# SparkFun_lsm9ds0-breakout.net
KiCad netlist of a schematic drawn in EAGLE
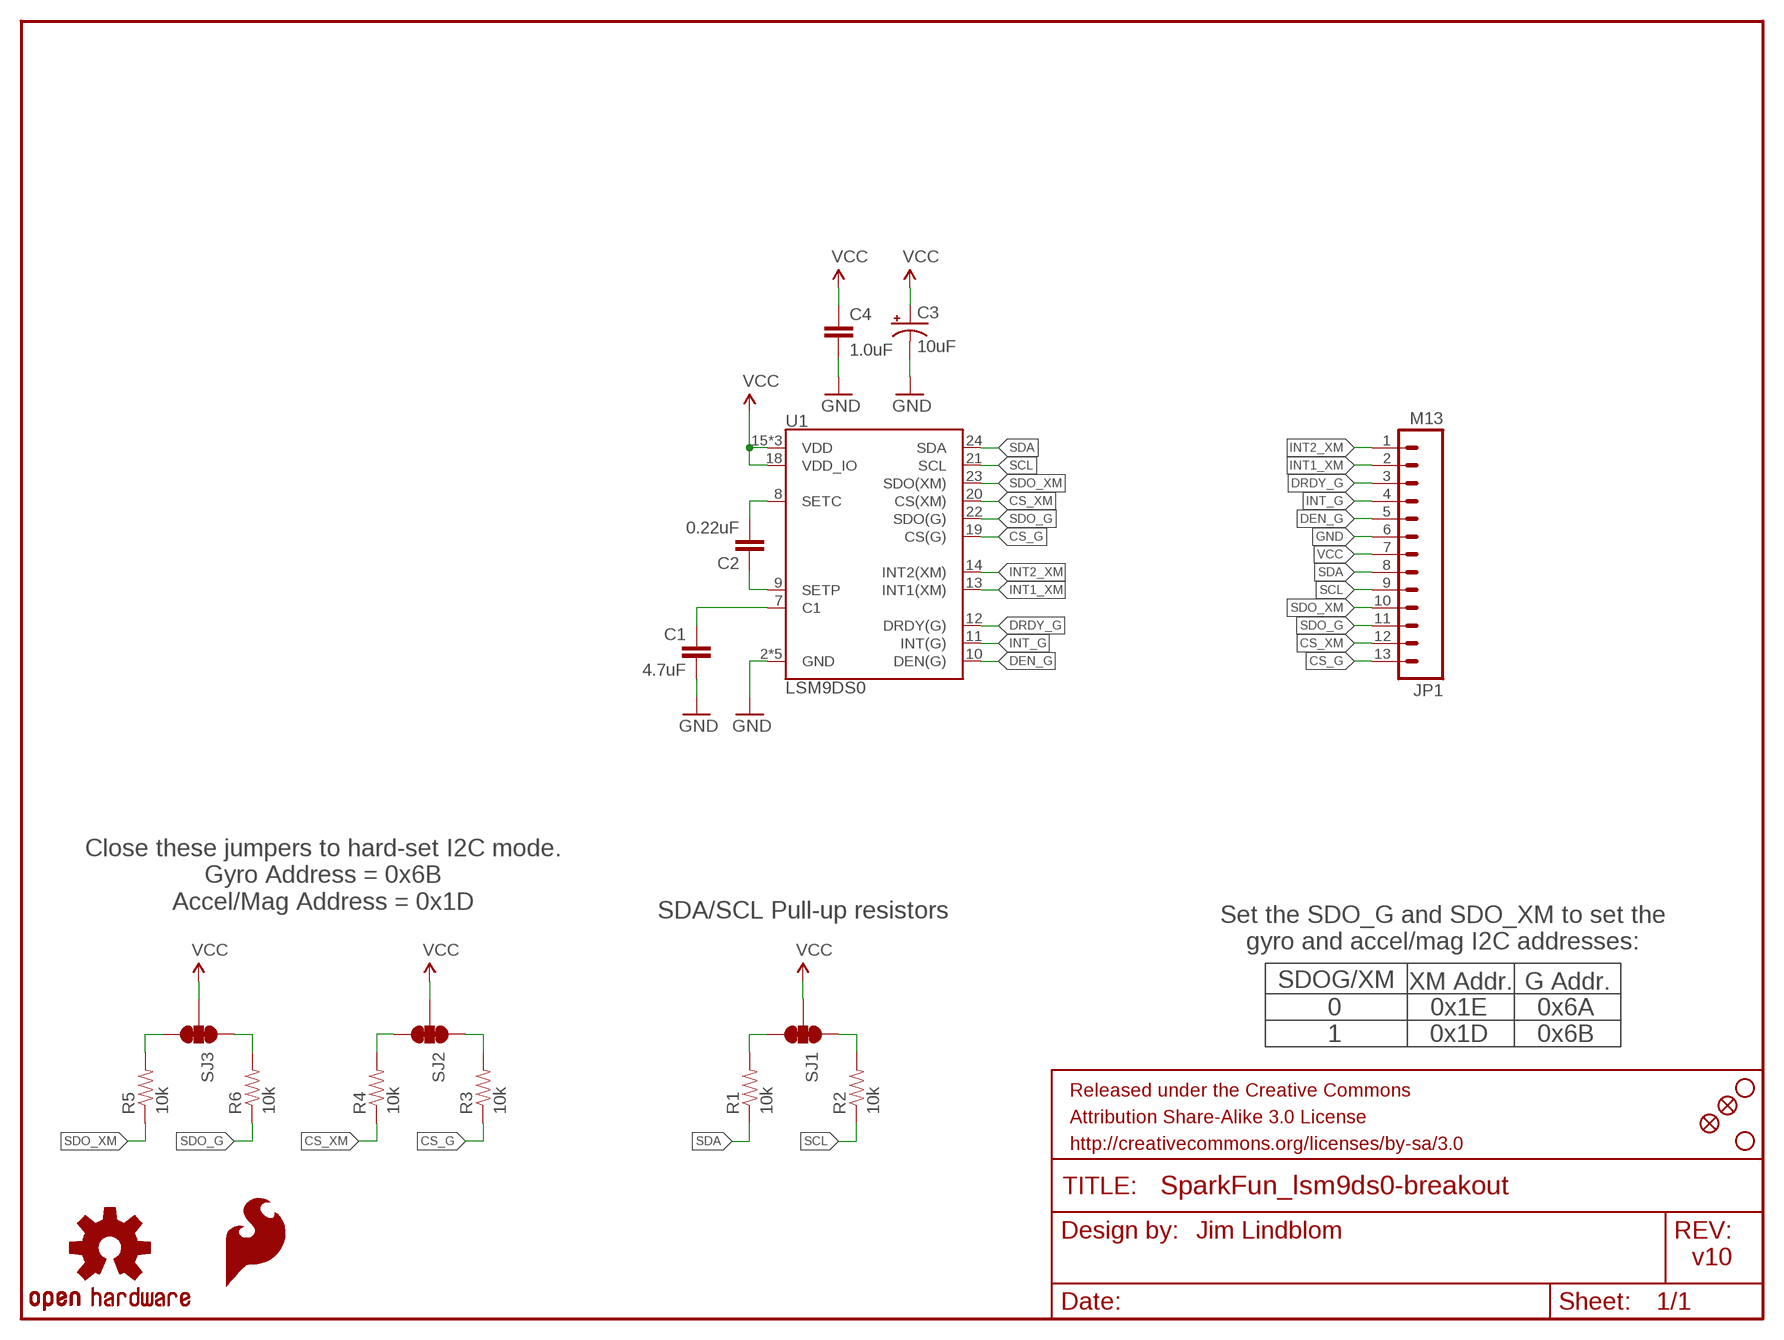
[diagram p0: schematic, sheet 1]

(export (version "E")
  (design (tool "Eeschema 10.0.6"))
  (components
    (comp (ref "C1")
      (value "4.7uF")
      (footprint "eagle-import:0603-CAP")
      (libsource (lib "eagle-import") (part "4.7UF-6.3V-10%(0603)0603"))
    )
    (comp (ref "C2")
      (value "0.22uF")
      (footprint "eagle-import:0603-CAP")
      (libsource (lib "eagle-import") (part "0.22UF-25V-10%(0603)"))
    )
    (comp (ref "C3")
      (value "10uF")
      (footprint "eagle-import:EIA3216")
      (libsource (lib "eagle-import") (part "10UF-16V-10%(TANT)"))
    )
    (comp (ref "C4")
      (value "1.0uF")
      (footprint "eagle-import:0603-CAP")
      (libsource (lib "eagle-import") (part "1.0UF-16V-10%(0603)"))
    )
    (comp (ref "FID1")
      (value "FIDUCIALUFIDUCIAL")
      (footprint "eagle-import:MICRO-FIDUCIAL")
      (libsource (lib "eagle-import") (part "FIDUCIALUFIDUCIAL"))
    )
    (comp (ref "FID2")
      (value "FIDUCIALUFIDUCIAL")
      (footprint "eagle-import:MICRO-FIDUCIAL")
      (libsource (lib "eagle-import") (part "FIDUCIALUFIDUCIAL"))
    )
    (comp (ref "FRAME1")
      (value "FRAME-LETTER")
      (footprint "eagle-import:CREATIVE_COMMONS")
      (libsource (lib "eagle-import") (part "FRAME-LETTER"))
    )
    (comp (ref "JP1")
      (value "M13")
      (footprint "eagle-import:1X13")
      (libsource (lib "eagle-import") (part "M13"))
    )
    (comp (ref "LOGO1")
      (value "OSHW-LOGOS")
      (footprint "eagle-import:OSHW-LOGO-S")
      (libsource (lib "eagle-import") (part "OSHW-LOGOS"))
    )
    (comp (ref "LOGO2")
      (value "SFE_LOGO_FLAME.1_INCH")
      (footprint "eagle-import:SFE_LOGO_FLAME_.1")
      (libsource (lib "eagle-import") (part "SFE_LOGO_FLAME.1_INCH"))
    )
    (comp (ref "LOGO3")
      (value "SFE_LOGO_FLAME.1_INCH")
      (footprint "eagle-import:SFE_LOGO_FLAME_.1")
      (libsource (lib "eagle-import") (part "SFE_LOGO_FLAME.1_INCH"))
    )
    (comp (ref "R1")
      (value "10k")
      (footprint "eagle-import:0603-RES")
      (libsource (lib "eagle-import") (part "10K-1%RES-00824"))
    )
    (comp (ref "R2")
      (value "10k")
      (footprint "eagle-import:0603-RES")
      (libsource (lib "eagle-import") (part "10K-1%RES-00824"))
    )
    (comp (ref "R3")
      (value "10k")
      (footprint "eagle-import:0603-RES")
      (libsource (lib "eagle-import") (part "10K-1%RES-00824"))
    )
    (comp (ref "R4")
      (value "10k")
      (footprint "eagle-import:0603-RES")
      (libsource (lib "eagle-import") (part "10K-1%RES-00824"))
    )
    (comp (ref "R5")
      (value "10k")
      (footprint "eagle-import:0603-RES")
      (libsource (lib "eagle-import") (part "10K-1%RES-00824"))
    )
    (comp (ref "R6")
      (value "10k")
      (footprint "eagle-import:0603-RES")
      (libsource (lib "eagle-import") (part "10K-1%RES-00824"))
    )
    (comp (ref "SJ1")
      (value "SOLDERJUMPER_2WAYS")
      (footprint "eagle-import:SJ_3")
      (libsource (lib "eagle-import") (part "SOLDERJUMPER_2WAYS"))
    )
    (comp (ref "SJ2")
      (value "SOLDERJUMPER_2WAYS")
      (footprint "eagle-import:SJ_3")
      (libsource (lib "eagle-import") (part "SOLDERJUMPER_2WAYS"))
    )
    (comp (ref "SJ3")
      (value "SOLDERJUMPER_2WAYS")
      (footprint "eagle-import:SJ_3")
      (libsource (lib "eagle-import") (part "SOLDERJUMPER_2WAYS"))
    )
    (comp (ref "STANDOFF1")
      (value "STAND-OFF")
      (footprint "eagle-import:STAND-OFF")
      (libsource (lib "eagle-import") (part "STAND-OFF"))
    )
    (comp (ref "STANDOFF2")
      (value "STAND-OFF")
      (footprint "eagle-import:STAND-OFF")
      (libsource (lib "eagle-import") (part "STAND-OFF"))
    )
    (comp (ref "U1")
      (value "LSM9DS0")
      (footprint "eagle-import:LGA-24")
      (libsource (lib "eagle-import") (part "LSM9DS0"))
    )
  )
  (nets
    (net (code "1") (name "CS_G") (class "Default")
      (node (ref "JP1") (pin "13") (pinfunction "13_13") (pintype "passive"))
      (node (ref "R3") (pin "1") (pinfunction "1_1") (pintype "passive"))
      (node (ref "U1") (pin "19") (pinfunction "CS(G)_19") (pintype "bidirectional"))
    )
    (net (code "2") (name "CS_XM") (class "Default")
      (node (ref "JP1") (pin "12") (pinfunction "12_12") (pintype "passive"))
      (node (ref "R4") (pin "1") (pinfunction "1_1") (pintype "passive"))
      (node (ref "U1") (pin "20") (pinfunction "CS(XM)_20") (pintype "bidirectional"))
    )
    (net (code "3") (name "DEN_G") (class "Default")
      (node (ref "JP1") (pin "5") (pinfunction "5_5") (pintype "passive"))
      (node (ref "U1") (pin "10") (pinfunction "DEN(G)_10") (pintype "bidirectional"))
    )
    (net (code "4") (name "DRDY_G") (class "Default")
      (node (ref "JP1") (pin "3") (pinfunction "3_3") (pintype "passive"))
      (node (ref "U1") (pin "12") (pinfunction "DRDY(G)_12") (pintype "bidirectional"))
    )
    (net (code "5") (name "GND") (class "Default")
      (node (ref "C1") (pin "2") (pinfunction "2_2") (pintype "passive"))
      (node (ref "C3") (pin "C") (pinfunction "-_C") (pintype "passive"))
      (node (ref "C4") (pin "2") (pinfunction "2_2") (pintype "passive"))
      (node (ref "JP1") (pin "6") (pinfunction "6_6") (pintype "passive"))
      (node (ref "U1") (pin "2") (pinfunction "GND_2") (pintype "bidirectional"))
      (node (ref "U1") (pin "3") (pinfunction "GND_3") (pintype "bidirectional"))
      (node (ref "U1") (pin "4") (pinfunction "GND_4") (pintype "bidirectional"))
      (node (ref "U1") (pin "5") (pinfunction "GND_5") (pintype "bidirectional"))
      (node (ref "U1") (pin "6") (pinfunction "GND_6") (pintype "bidirectional"))
    )
    (net (code "6") (name "INT1_XM") (class "Default")
      (node (ref "JP1") (pin "2") (pinfunction "2_2") (pintype "passive"))
      (node (ref "U1") (pin "13") (pinfunction "INT1(XM)_13") (pintype "bidirectional"))
    )
    (net (code "7") (name "INT2_XM") (class "Default")
      (node (ref "JP1") (pin "1") (pinfunction "1_1") (pintype "passive"))
      (node (ref "U1") (pin "14") (pinfunction "INT2(XM)_14") (pintype "bidirectional"))
    )
    (net (code "8") (name "INT_G") (class "Default")
      (node (ref "JP1") (pin "4") (pinfunction "4_4") (pintype "passive"))
      (node (ref "U1") (pin "11") (pinfunction "INT(G)_11") (pintype "bidirectional"))
    )
    (net (code "9") (name "Net-(R1-Pad2)") (class "Default")
      (node (ref "R1") (pin "2") (pinfunction "2_2") (pintype "passive"))
      (node (ref "SJ1") (pin "3") (pinfunction "3_3") (pintype "passive"))
    )
    (net (code "10") (name "Net-(R2-Pad2)") (class "Default")
      (node (ref "R2") (pin "2") (pinfunction "2_2") (pintype "passive"))
      (node (ref "SJ1") (pin "1") (pinfunction "1_1") (pintype "passive"))
    )
    (net (code "11") (name "Net-(R3-Pad2)") (class "Default")
      (node (ref "R3") (pin "2") (pinfunction "2_2") (pintype "passive"))
      (node (ref "SJ2") (pin "1") (pinfunction "1_1") (pintype "passive"))
    )
    (net (code "12") (name "Net-(R4-Pad2)") (class "Default")
      (node (ref "R4") (pin "2") (pinfunction "2_2") (pintype "passive"))
      (node (ref "SJ2") (pin "3") (pinfunction "3_3") (pintype "passive"))
    )
    (net (code "13") (name "Net-(R5-Pad2)") (class "Default")
      (node (ref "R5") (pin "2") (pinfunction "2_2") (pintype "passive"))
      (node (ref "SJ3") (pin "3") (pinfunction "3_3") (pintype "passive"))
    )
    (net (code "14") (name "Net-(R6-Pad2)") (class "Default")
      (node (ref "R6") (pin "2") (pinfunction "2_2") (pintype "passive"))
      (node (ref "SJ3") (pin "1") (pinfunction "1_1") (pintype "passive"))
    )
    (net (code "15") (name "Net-(U1-C1)") (class "Default")
      (node (ref "C1") (pin "1") (pinfunction "1_1") (pintype "passive"))
      (node (ref "U1") (pin "7") (pinfunction "C1_7") (pintype "bidirectional"))
    )
    (net (code "16") (name "Net-(U1-SETC)") (class "Default")
      (node (ref "C2") (pin "2") (pinfunction "2_2") (pintype "passive"))
      (node (ref "U1") (pin "8") (pinfunction "SETC_8") (pintype "bidirectional"))
    )
    (net (code "17") (name "Net-(U1-SETP)") (class "Default")
      (node (ref "C2") (pin "1") (pinfunction "1_1") (pintype "passive"))
      (node (ref "U1") (pin "9") (pinfunction "SETP_9") (pintype "bidirectional"))
    )
    (net (code "18") (name "SCL") (class "Default")
      (node (ref "JP1") (pin "9") (pinfunction "9_9") (pintype "passive"))
      (node (ref "R2") (pin "1") (pinfunction "1_1") (pintype "passive"))
      (node (ref "U1") (pin "21") (pinfunction "SCL_21") (pintype "bidirectional"))
    )
    (net (code "19") (name "SDA") (class "Default")
      (node (ref "JP1") (pin "8") (pinfunction "8_8") (pintype "passive"))
      (node (ref "R1") (pin "1") (pinfunction "1_1") (pintype "passive"))
      (node (ref "U1") (pin "24") (pinfunction "SDA_24") (pintype "bidirectional"))
    )
    (net (code "20") (name "SDO_G") (class "Default")
      (node (ref "JP1") (pin "11") (pinfunction "11_11") (pintype "passive"))
      (node (ref "R6") (pin "1") (pinfunction "1_1") (pintype "passive"))
      (node (ref "U1") (pin "22") (pinfunction "SDO(G)_22") (pintype "bidirectional"))
    )
    (net (code "21") (name "SDO_XM") (class "Default")
      (node (ref "JP1") (pin "10") (pinfunction "10_10") (pintype "passive"))
      (node (ref "R5") (pin "1") (pinfunction "1_1") (pintype "passive"))
      (node (ref "U1") (pin "23") (pinfunction "SDO(XM)_23") (pintype "bidirectional"))
    )
    (net (code "22") (name "VCC") (class "Default")
      (node (ref "C3") (pin "A") (pinfunction "+_A") (pintype "passive"))
      (node (ref "C4") (pin "1") (pinfunction "1_1") (pintype "passive"))
      (node (ref "JP1") (pin "7") (pinfunction "7_7") (pintype "passive"))
      (node (ref "SJ1") (pin "2") (pinfunction "2_2") (pintype "passive"))
      (node (ref "SJ2") (pin "2") (pinfunction "2_2") (pintype "passive"))
      (node (ref "SJ3") (pin "2") (pinfunction "2_2") (pintype "passive"))
      (node (ref "U1") (pin "15") (pinfunction "VDD_15") (pintype "bidirectional"))
      (node (ref "U1") (pin "16") (pinfunction "VDD_16") (pintype "bidirectional"))
      (node (ref "U1") (pin "17") (pinfunction "VDD_17") (pintype "bidirectional"))
      (node (ref "U1") (pin "18") (pinfunction "VDD_IO_18") (pintype "bidirectional"))
    )
  )
)
